# circuit.net
KiCad netlist of a schematic drawn in EAGLE
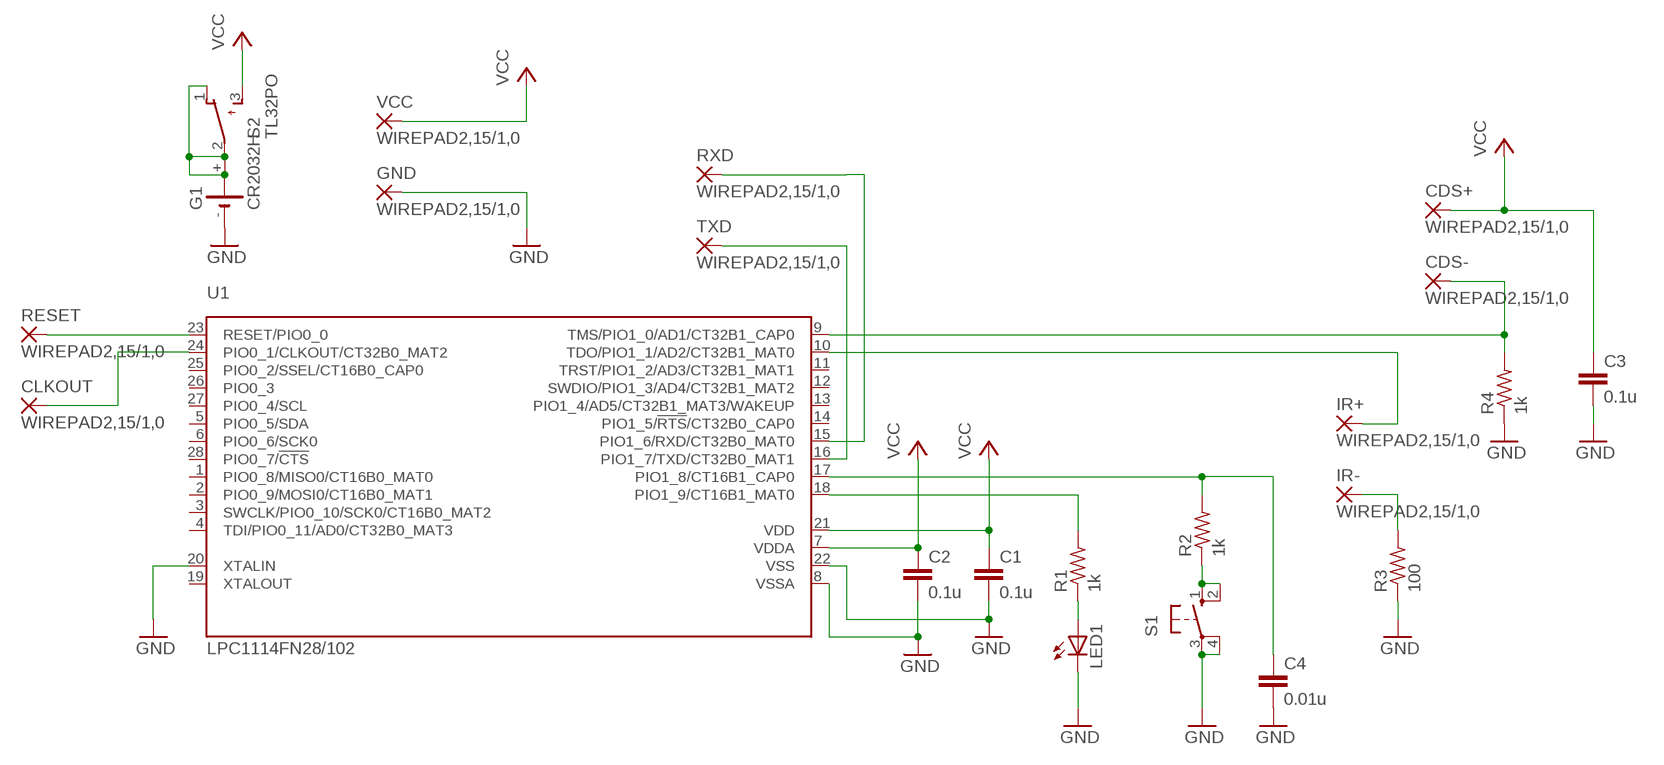
[diagram p0: schematic, sheet 1]

(export (version "E")
  (design (tool "Eeschema 10.0.6"))
  (components
    (comp (ref "C1")
      (value "0.1u")
      (footprint "eagle-import:C025-024X044")
      (libsource (lib "eagle-import") (part "C-EU025-024X044"))
    )
    (comp (ref "C2")
      (value "0.1u")
      (footprint "eagle-import:C025-024X044")
      (libsource (lib "eagle-import") (part "C-EU025-024X044"))
    )
    (comp (ref "C3")
      (value "0.1u")
      (footprint "eagle-import:C025-024X044")
      (libsource (lib "eagle-import") (part "C-EU025-024X044"))
    )
    (comp (ref "C4")
      (value "0.01u")
      (footprint "eagle-import:C025-024X044")
      (libsource (lib "eagle-import") (part "C-EU025-024X044"))
    )
    (comp (ref "CDS+")
      (value "WIREPAD2,15/1,0")
      (footprint "eagle-import:2,15_1,0")
      (libsource (lib "eagle-import") (part "WIREPAD2,15/1,0"))
    )
    (comp (ref "CDS-")
      (value "WIREPAD2,15/1,0")
      (footprint "eagle-import:2,15_1,0")
      (libsource (lib "eagle-import") (part "WIREPAD2,15/1,0"))
    )
    (comp (ref "CLKOUT")
      (value "WIREPAD2,15/1,0")
      (footprint "eagle-import:2,15_1,0")
      (libsource (lib "eagle-import") (part "WIREPAD2,15/1,0"))
    )
    (comp (ref "G1")
      (value "CR2032H")
      (footprint "eagle-import:CR2032H")
      (libsource (lib "eagle-import") (part "CR2032H"))
    )
    (comp (ref "GND")
      (value "WIREPAD2,15/1,0")
      (footprint "eagle-import:2,15_1,0")
      (libsource (lib "eagle-import") (part "WIREPAD2,15/1,0"))
    )
    (comp (ref "IR+")
      (value "WIREPAD2,15/1,0")
      (footprint "eagle-import:2,15_1,0")
      (libsource (lib "eagle-import") (part "WIREPAD2,15/1,0"))
    )
    (comp (ref "IR-")
      (value "WIREPAD2,15/1,0")
      (footprint "eagle-import:2,15_1,0")
      (libsource (lib "eagle-import") (part "WIREPAD2,15/1,0"))
    )
    (comp (ref "LED1")
      (value "LED5MM")
      (footprint "eagle-import:LED5MM")
      (libsource (lib "eagle-import") (part "LED5MM"))
    )
    (comp (ref "R1")
      (value "1k")
      (footprint "eagle-import:0204_7")
      (libsource (lib "eagle-import") (part "R-US_0204/7"))
    )
    (comp (ref "R2")
      (value "1k")
      (footprint "eagle-import:0204_7")
      (libsource (lib "eagle-import") (part "R-US_0204/7"))
    )
    (comp (ref "R3")
      (value "100")
      (footprint "eagle-import:0204_7")
      (libsource (lib "eagle-import") (part "R-US_0204/7"))
    )
    (comp (ref "R4")
      (value "1k")
      (footprint "eagle-import:0204_7")
      (libsource (lib "eagle-import") (part "R-US_0204/7"))
    )
    (comp (ref "RESET")
      (value "WIREPAD2,15/1,0")
      (footprint "eagle-import:2,15_1,0")
      (libsource (lib "eagle-import") (part "WIREPAD2,15/1,0"))
    )
    (comp (ref "RXD")
      (value "WIREPAD2,15/1,0")
      (footprint "eagle-import:2,15_1,0")
      (libsource (lib "eagle-import") (part "WIREPAD2,15/1,0"))
    )
    (comp (ref "S1")
      (value "10-XX")
      (footprint "eagle-import:B3F-10XX")
      (fields (field (name "MPN") "B3F-1000"))
      (libsource (lib "eagle-import") (part "10-XX"))
    )
    (comp (ref "S2")
      (value "TL32PO")
      (footprint "eagle-import:TL3XPO")
      (libsource (lib "eagle-import") (part "TL32PO"))
    )
    (comp (ref "TXD")
      (value "WIREPAD2,15/1,0")
      (footprint "eagle-import:2,15_1,0")
      (libsource (lib "eagle-import") (part "WIREPAD2,15/1,0"))
    )
    (comp (ref "U1")
      (value "LPC1114FN28/102")
      (footprint "eagle-import:SOT117")
      (libsource (lib "eagle-import") (part "LPC1114FN28/102"))
    )
    (comp (ref "VCC")
      (value "WIREPAD2,15/1,0")
      (footprint "eagle-import:2,15_1,0")
      (libsource (lib "eagle-import") (part "WIREPAD2,15/1,0"))
    )
  )
  (nets
    (net (code "1") (name "GND") (class "Default")
      (node (ref "C1") (pin "2") (pinfunction "2_2") (pintype "passive"))
      (node (ref "C2") (pin "2") (pinfunction "2_2") (pintype "passive"))
      (node (ref "C3") (pin "2") (pinfunction "2_2") (pintype "passive"))
      (node (ref "C4") (pin "2") (pinfunction "2_2") (pintype "passive"))
      (node (ref "G1") (pin "-") (pinfunction "-_-") (pintype "passive"))
      (node (ref "GND") (pin "1") (pinfunction "P_1") (pintype "passive"))
      (node (ref "LED1") (pin "K") (pinfunction "C_K") (pintype "passive"))
      (node (ref "R3") (pin "1") (pinfunction "1_1") (pintype "passive"))
      (node (ref "R4") (pin "1") (pinfunction "1_1") (pintype "passive"))
      (node (ref "S1") (pin "3") (pinfunction "P_3") (pintype "passive"))
      (node (ref "S1") (pin "4") (pinfunction "P1_4") (pintype "passive"))
      (node (ref "U1") (pin "20") (pinfunction "XTALIN_20") (pintype "input"))
      (node (ref "U1") (pin "22") (pinfunction "VSS_22") (pintype "power_in"))
      (node (ref "U1") (pin "8") (pinfunction "VSSA_8") (pintype "power_in"))
    )
    (net (code "2") (name "Net-(CDS--P)") (class "Default")
      (node (ref "CDS-") (pin "1") (pinfunction "P_1") (pintype "passive"))
      (node (ref "R4") (pin "2") (pinfunction "2_2") (pintype "passive"))
      (node (ref "U1") (pin "9") (pinfunction "TMS/PIO1_0/AD1/CT32B1_CAP0_9") (pintype "bidirectional"))
    )
    (net (code "3") (name "Net-(CLKOUT-P)") (class "Default")
      (node (ref "CLKOUT") (pin "1") (pinfunction "P_1") (pintype "passive"))
      (node (ref "U1") (pin "24") (pinfunction "PIO0_1/CLKOUT/CT32B0_MAT2_24") (pintype "bidirectional"))
    )
    (net (code "4") (name "Net-(IR+-P)") (class "Default")
      (node (ref "IR+") (pin "1") (pinfunction "P_1") (pintype "passive"))
      (node (ref "U1") (pin "10") (pinfunction "TDO/PIO1_1/AD2/CT32B1_MAT0_10") (pintype "bidirectional"))
    )
    (net (code "5") (name "Net-(IR--P)") (class "Default")
      (node (ref "IR-") (pin "1") (pinfunction "P_1") (pintype "passive"))
      (node (ref "R3") (pin "2") (pinfunction "2_2") (pintype "passive"))
    )
    (net (code "6") (name "Net-(LED1-PadA)") (class "Default")
      (node (ref "LED1") (pin "A") (pinfunction "A_A") (pintype "passive"))
      (node (ref "R1") (pin "1") (pinfunction "1_1") (pintype "passive"))
    )
    (net (code "7") (name "Net-(RESET-P)") (class "Default")
      (node (ref "RESET") (pin "1") (pinfunction "P_1") (pintype "passive"))
      (node (ref "U1") (pin "23") (pinfunction "RESET/PIO0_0_23") (pintype "bidirectional"))
    )
    (net (code "8") (name "Net-(RXD-P)") (class "Default")
      (node (ref "RXD") (pin "1") (pinfunction "P_1") (pintype "passive"))
      (node (ref "U1") (pin "15") (pinfunction "PIO1_6/RXD/CT32B0_MAT0_15") (pintype "bidirectional"))
    )
    (net (code "9") (name "Net-(S1-S)") (class "Default")
      (node (ref "R2") (pin "1") (pinfunction "1_1") (pintype "passive"))
      (node (ref "S1") (pin "1") (pinfunction "S_1") (pintype "passive"))
      (node (ref "S1") (pin "2") (pinfunction "S1_2") (pintype "passive"))
    )
    (net (code "10") (name "Net-(S2-O)") (class "Default")
      (node (ref "G1") (pin "+") (pinfunction "+_+") (pintype "passive"))
      (node (ref "G1") (pin "+@1") (pinfunction "+_+@1") (pintype "passive"))
      (node (ref "S2") (pin "1") (pinfunction "O_1") (pintype "passive"))
      (node (ref "S2") (pin "2") (pinfunction "P_2") (pintype "passive"))
    )
    (net (code "11") (name "Net-(TXD-P)") (class "Default")
      (node (ref "TXD") (pin "1") (pinfunction "P_1") (pintype "passive"))
      (node (ref "U1") (pin "16") (pinfunction "PIO1_7/TXD/CT32B0_MAT1_16") (pintype "bidirectional"))
    )
    (net (code "12") (name "Net-(U1-PIO1_8{slash}CT16B1_CAP0)") (class "Default")
      (node (ref "C4") (pin "1") (pinfunction "1_1") (pintype "passive"))
      (node (ref "R2") (pin "2") (pinfunction "2_2") (pintype "passive"))
      (node (ref "U1") (pin "17") (pinfunction "PIO1_8/CT16B1_CAP0_17") (pintype "bidirectional"))
    )
    (net (code "13") (name "Net-(U1-PIO1_9{slash}CT16B1_MAT0)") (class "Default")
      (node (ref "R1") (pin "2") (pinfunction "2_2") (pintype "passive"))
      (node (ref "U1") (pin "18") (pinfunction "PIO1_9/CT16B1_MAT0_18") (pintype "bidirectional"))
    )
    (net (code "14") (name "VCC") (class "Default")
      (node (ref "C1") (pin "1") (pinfunction "1_1") (pintype "passive"))
      (node (ref "C2") (pin "1") (pinfunction "1_1") (pintype "passive"))
      (node (ref "C3") (pin "1") (pinfunction "1_1") (pintype "passive"))
      (node (ref "CDS+") (pin "1") (pinfunction "P_1") (pintype "passive"))
      (node (ref "S2") (pin "3") (pinfunction "S_3") (pintype "passive"))
      (node (ref "U1") (pin "21") (pinfunction "VDD_21") (pintype "power_in"))
      (node (ref "U1") (pin "7") (pinfunction "VDDA_7") (pintype "power_in"))
      (node (ref "VCC") (pin "1") (pinfunction "P_1") (pintype "passive"))
    )
    (net (code "15") (name "unconnected-(U1-PIO0_2{slash}SSEL{slash}CT16B0_CAP0-Pad25)") (class "Default")
      (node (ref "U1") (pin "25") (pinfunction "PIO0_2/SSEL/CT16B0_CAP0_25") (pintype "bidirectional"))
    )
    (net (code "16") (name "unconnected-(U1-PIO0_3-Pad26)") (class "Default")
      (node (ref "U1") (pin "26") (pinfunction "PIO0_3_26") (pintype "bidirectional"))
    )
    (net (code "17") (name "unconnected-(U1-PIO0_4{slash}SCL-Pad27)") (class "Default")
      (node (ref "U1") (pin "27") (pinfunction "PIO0_4/SCL_27") (pintype "bidirectional"))
    )
    (net (code "18") (name "unconnected-(U1-PIO0_5{slash}SDA-Pad5)") (class "Default")
      (node (ref "U1") (pin "5") (pinfunction "PIO0_5/SDA_5") (pintype "bidirectional"))
    )
    (net (code "19") (name "unconnected-(U1-PIO0_6{slash}SCK0-Pad6)") (class "Default")
      (node (ref "U1") (pin "6") (pinfunction "PIO0_6/SCK0_6") (pintype "bidirectional"))
    )
    (net (code "20") (name "unconnected-(U1-PIO0_7{slash}~{CTS}-Pad28)") (class "Default")
      (node (ref "U1") (pin "28") (pinfunction "PIO0_7/~{CTS}_28") (pintype "bidirectional"))
    )
    (net (code "21") (name "unconnected-(U1-PIO0_8{slash}MISO0{slash}CT16B0_MAT0-Pad1)") (class "Default")
      (node (ref "U1") (pin "1") (pinfunction "PIO0_8/MISO0/CT16B0_MAT0_1") (pintype "bidirectional"))
    )
    (net (code "22") (name "unconnected-(U1-PIO0_9{slash}MOSI0{slash}CT16B0_MAT1-Pad2)") (class "Default")
      (node (ref "U1") (pin "2") (pinfunction "PIO0_9/MOSI0/CT16B0_MAT1_2") (pintype "bidirectional"))
    )
    (net (code "23") (name "unconnected-(U1-PIO1_4{slash}AD5{slash}CT32B1_MAT3{slash}WAKEUP-Pad13)") (class "Default")
      (node (ref "U1") (pin "13") (pinfunction "PIO1_4/AD5/CT32B1_MAT3/WAKEUP_13") (pintype "bidirectional"))
    )
    (net (code "24") (name "unconnected-(U1-PIO1_5{slash}~{RTS}{slash}CT32B0_CAP0-Pad14)") (class "Default")
      (node (ref "U1") (pin "14") (pinfunction "PIO1_5/~{RTS}/CT32B0_CAP0_14") (pintype "bidirectional"))
    )
    (net (code "25") (name "unconnected-(U1-SWCLK{slash}PIO0_10{slash}SCK0{slash}CT16B0_MAT2-Pad3)") (class "Default")
      (node (ref "U1") (pin "3") (pinfunction "SWCLK/PIO0_10/SCK0/CT16B0_MAT2_3") (pintype "bidirectional"))
    )
    (net (code "26") (name "unconnected-(U1-SWDIO{slash}PIO1_3{slash}AD4{slash}CT32B1_MAT2-Pad12)") (class "Default")
      (node (ref "U1") (pin "12") (pinfunction "SWDIO/PIO1_3/AD4/CT32B1_MAT2_12") (pintype "bidirectional"))
    )
    (net (code "27") (name "unconnected-(U1-TDI{slash}PIO0_11{slash}AD0{slash}CT32B0_MAT3-Pad4)") (class "Default")
      (node (ref "U1") (pin "4") (pinfunction "TDI/PIO0_11/AD0/CT32B0_MAT3_4") (pintype "bidirectional"))
    )
    (net (code "28") (name "unconnected-(U1-TRST{slash}PIO1_2{slash}AD3{slash}CT32B1_MAT1-Pad11)") (class "Default")
      (node (ref "U1") (pin "11") (pinfunction "TRST/PIO1_2/AD3/CT32B1_MAT1_11") (pintype "bidirectional"))
    )
    (net (code "29") (name "unconnected-(U1-XTALOUT-Pad19)") (class "Default")
      (node (ref "U1") (pin "19") (pinfunction "XTALOUT_19") (pintype "output"))
    )
  )
)
